# Door-opener.net
KiCad netlist of a schematic drawn in EAGLE
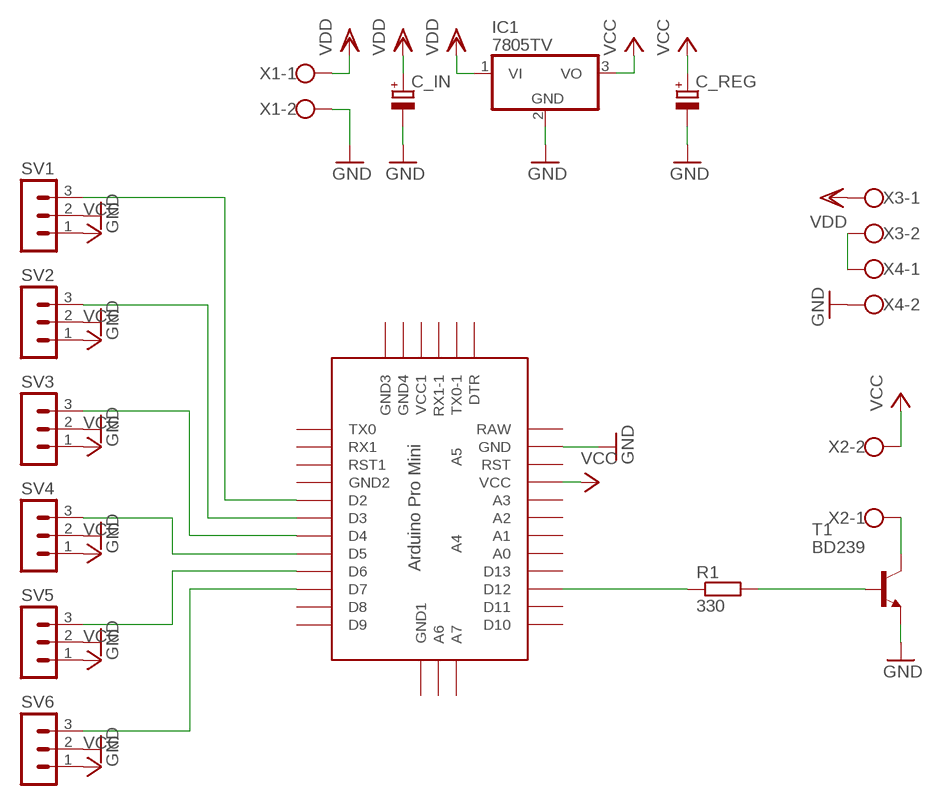
[diagram p0: schematic, sheet 1]

(export (version "E")
  (design (tool "Eeschema 10.0.6"))
  (components
    (comp (ref "C_IN")
      (value "CPOL-EUE3.5-8")
      (footprint "eagle-import:E3,5-8")
      (libsource (lib "eagle-import") (part "CPOL-EUE3.5-8"))
    )
    (comp (ref "C_REG")
      (value "CPOL-EUE3.5-8")
      (footprint "eagle-import:E3,5-8")
      (libsource (lib "eagle-import") (part "CPOL-EUE3.5-8"))
    )
    (comp (ref "IC1")
      (value "7805TV")
      (footprint "eagle-import:TO220V")
      (libsource (lib "eagle-import") (part "78TV05"))
    )
    (comp (ref "R1")
      (value "330")
      (footprint "eagle-import:0207_10")
      (libsource (lib "eagle-import") (part "R-EU_0207/10"))
    )
    (comp (ref "SV1")
      (value "MA03-1")
      (footprint "eagle-import:MA03-1")
      (libsource (lib "eagle-import") (part "MA03-1"))
    )
    (comp (ref "SV2")
      (value "MA03-1")
      (footprint "eagle-import:MA03-1")
      (libsource (lib "eagle-import") (part "MA03-1"))
    )
    (comp (ref "SV3")
      (value "MA03-1")
      (footprint "eagle-import:MA03-1")
      (libsource (lib "eagle-import") (part "MA03-1"))
    )
    (comp (ref "SV4")
      (value "MA03-1")
      (footprint "eagle-import:MA03-1")
      (libsource (lib "eagle-import") (part "MA03-1"))
    )
    (comp (ref "SV5")
      (value "MA03-1")
      (footprint "eagle-import:MA03-1")
      (libsource (lib "eagle-import") (part "MA03-1"))
    )
    (comp (ref "SV6")
      (value "MA03-1")
      (footprint "eagle-import:MA03-1")
      (libsource (lib "eagle-import") (part "MA03-1"))
    )
    (comp (ref "T1")
      (value "BD239")
      (footprint "eagle-import:TO220")
      (libsource (lib "eagle-import") (part "BD239"))
    )
    (comp (ref "U$1")
      (value "ABK-PRO-MINI")
      (footprint "eagle-import:ABK-PRO-MINI")
      (libsource (lib "eagle-import") (part "ABK-PRO-MINI"))
    )
    (comp (ref "X1")
      (value "W237-102")
      (footprint "eagle-import:W237-102")
      (fields (field (name "MPN") "237-102"))
      (libsource (lib "eagle-import") (part "W237-102"))
    )
    (comp (ref "X2")
      (value "W237-102")
      (footprint "eagle-import:W237-102")
      (fields (field (name "MPN") "237-102"))
      (libsource (lib "eagle-import") (part "W237-102"))
    )
    (comp (ref "X3")
      (value "W237-102")
      (footprint "eagle-import:W237-102")
      (fields (field (name "MPN") "237-102"))
      (libsource (lib "eagle-import") (part "W237-102"))
    )
    (comp (ref "X4")
      (value "W237-102")
      (footprint "eagle-import:W237-102")
      (fields (field (name "MPN") "237-102"))
      (libsource (lib "eagle-import") (part "W237-102"))
    )
  )
  (nets
    (net (code "1") (name "GND") (class "Default")
      (node (ref "C_IN") (pin "-") (pinfunction "-_-") (pintype "passive"))
      (node (ref "C_REG") (pin "-") (pinfunction "-_-") (pintype "passive"))
      (node (ref "IC1") (pin "2") (pinfunction "GND_2") (pintype "passive"))
      (node (ref "SV1") (pin "2") (pinfunction "2_2") (pintype "passive"))
      (node (ref "SV2") (pin "2") (pinfunction "2_2") (pintype "passive"))
      (node (ref "SV3") (pin "2") (pinfunction "2_2") (pintype "passive"))
      (node (ref "SV4") (pin "2") (pinfunction "2_2") (pintype "passive"))
      (node (ref "SV5") (pin "2") (pinfunction "2_2") (pintype "passive"))
      (node (ref "SV6") (pin "2") (pinfunction "2_2") (pintype "passive"))
      (node (ref "T1") (pin "3") (pinfunction "E_3") (pintype "passive"))
      (node (ref "U$1") (pin "GND") (pinfunction "GND_GND") (pintype "bidirectional"))
      (node (ref "X1") (pin "2") (pinfunction "KL_2") (pintype "passive"))
      (node (ref "X4") (pin "2") (pinfunction "KL_2") (pintype "passive"))
    )
    (net (code "2") (name "Net-(R1-Pad1)") (class "Default")
      (node (ref "R1") (pin "1") (pinfunction "1_1") (pintype "passive"))
      (node (ref "U$1") (pin "D12") (pinfunction "D12_D12") (pintype "bidirectional"))
    )
    (net (code "3") (name "Net-(SV1-Pad3)") (class "Default")
      (node (ref "SV1") (pin "3") (pinfunction "3_3") (pintype "passive"))
      (node (ref "U$1") (pin "D2") (pinfunction "D2_D2") (pintype "bidirectional"))
    )
    (net (code "4") (name "Net-(SV2-Pad3)") (class "Default")
      (node (ref "SV2") (pin "3") (pinfunction "3_3") (pintype "passive"))
      (node (ref "U$1") (pin "D3") (pinfunction "D3_D3") (pintype "bidirectional"))
    )
    (net (code "5") (name "Net-(SV3-Pad3)") (class "Default")
      (node (ref "SV3") (pin "3") (pinfunction "3_3") (pintype "passive"))
      (node (ref "U$1") (pin "D4") (pinfunction "D4_D4") (pintype "bidirectional"))
    )
    (net (code "6") (name "Net-(SV4-Pad3)") (class "Default")
      (node (ref "SV4") (pin "3") (pinfunction "3_3") (pintype "passive"))
      (node (ref "U$1") (pin "D5") (pinfunction "D5_D5") (pintype "bidirectional"))
    )
    (net (code "7") (name "Net-(SV5-Pad3)") (class "Default")
      (node (ref "SV5") (pin "3") (pinfunction "3_3") (pintype "passive"))
      (node (ref "U$1") (pin "D6") (pinfunction "D6_D6") (pintype "bidirectional"))
    )
    (net (code "8") (name "Net-(SV6-Pad3)") (class "Default")
      (node (ref "SV6") (pin "3") (pinfunction "3_3") (pintype "passive"))
      (node (ref "U$1") (pin "D7") (pinfunction "D7_D7") (pintype "bidirectional"))
    )
    (net (code "9") (name "Net-(T1-B)") (class "Default")
      (node (ref "R1") (pin "2") (pinfunction "2_2") (pintype "passive"))
      (node (ref "T1") (pin "1") (pinfunction "B_1") (pintype "passive"))
    )
    (net (code "10") (name "Net-(T1-C)") (class "Default")
      (node (ref "T1") (pin "2") (pinfunction "C_2") (pintype "passive"))
      (node (ref "X2") (pin "1") (pinfunction "KL_1") (pintype "passive"))
    )
    (net (code "11") (name "Net-(X3B-KL)") (class "Default")
      (node (ref "X3") (pin "2") (pinfunction "KL_2") (pintype "passive"))
      (node (ref "X4") (pin "1") (pinfunction "KL_1") (pintype "passive"))
    )
    (net (code "12") (name "VCC") (class "Default")
      (node (ref "C_REG") (pin "+") (pinfunction "+_+") (pintype "passive"))
      (node (ref "IC1") (pin "3") (pinfunction "VO_3") (pintype "passive"))
      (node (ref "SV1") (pin "1") (pinfunction "1_1") (pintype "passive"))
      (node (ref "SV2") (pin "1") (pinfunction "1_1") (pintype "passive"))
      (node (ref "SV3") (pin "1") (pinfunction "1_1") (pintype "passive"))
      (node (ref "SV4") (pin "1") (pinfunction "1_1") (pintype "passive"))
      (node (ref "SV5") (pin "1") (pinfunction "1_1") (pintype "passive"))
      (node (ref "SV6") (pin "1") (pinfunction "1_1") (pintype "passive"))
      (node (ref "U$1") (pin "VCC") (pinfunction "VCC_VCC") (pintype "bidirectional"))
      (node (ref "X2") (pin "2") (pinfunction "KL_2") (pintype "passive"))
    )
    (net (code "13") (name "VDD") (class "Default")
      (node (ref "C_IN") (pin "+") (pinfunction "+_+") (pintype "passive"))
      (node (ref "IC1") (pin "1") (pinfunction "VI_1") (pintype "input"))
      (node (ref "X1") (pin "1") (pinfunction "KL_1") (pintype "passive"))
      (node (ref "X3") (pin "1") (pinfunction "KL_1") (pintype "passive"))
    )
    (net (code "14") (name "unconnected-(U$1-GND1-PadGND4)") (class "Default")
      (node (ref "U$1") (pin "GND4") (pinfunction "GND1_GND4") (pintype "bidirectional"))
    )
    (net (code "15") (name "unconnected-(U$1-GND2-PadGND1)") (class "Default")
      (node (ref "U$1") (pin "GND1") (pinfunction "GND2_GND1") (pintype "bidirectional"))
    )
    (net (code "16") (name "unconnected-(U$1-GND3-PadGND2)") (class "Default")
      (node (ref "U$1") (pin "GND2") (pinfunction "GND3_GND2") (pintype "bidirectional"))
    )
    (net (code "17") (name "unconnected-(U$1-GND4-PadGND3)") (class "Default")
      (node (ref "U$1") (pin "GND3") (pinfunction "GND4_GND3") (pintype "bidirectional"))
    )
    (net (code "18") (name "unconnected-(U$1-PadA0)") (class "Default")
      (node (ref "U$1") (pin "A0") (pinfunction "A0_A0") (pintype "bidirectional"))
    )
    (net (code "19") (name "unconnected-(U$1-PadA1)") (class "Default")
      (node (ref "U$1") (pin "A1") (pinfunction "A1_A1") (pintype "bidirectional"))
    )
    (net (code "20") (name "unconnected-(U$1-PadA2)") (class "Default")
      (node (ref "U$1") (pin "A2") (pinfunction "A2_A2") (pintype "bidirectional"))
    )
    (net (code "21") (name "unconnected-(U$1-PadA3)") (class "Default")
      (node (ref "U$1") (pin "A3") (pinfunction "A3_A3") (pintype "bidirectional"))
    )
    (net (code "22") (name "unconnected-(U$1-PadA4)") (class "Default")
      (node (ref "U$1") (pin "A4") (pinfunction "A4_A4") (pintype "bidirectional"))
    )
    (net (code "23") (name "unconnected-(U$1-PadA5)") (class "Default")
      (node (ref "U$1") (pin "A5") (pinfunction "A5_A5") (pintype "bidirectional"))
    )
    (net (code "24") (name "unconnected-(U$1-PadA6)") (class "Default")
      (node (ref "U$1") (pin "A6") (pinfunction "A6_A6") (pintype "bidirectional"))
    )
    (net (code "25") (name "unconnected-(U$1-PadA7)") (class "Default")
      (node (ref "U$1") (pin "A7") (pinfunction "A7_A7") (pintype "bidirectional"))
    )
    (net (code "26") (name "unconnected-(U$1-PadD8)") (class "Default")
      (node (ref "U$1") (pin "D8") (pinfunction "D8_D8") (pintype "bidirectional"))
    )
    (net (code "27") (name "unconnected-(U$1-PadD9)") (class "Default")
      (node (ref "U$1") (pin "D9") (pinfunction "D9_D9") (pintype "bidirectional"))
    )
    (net (code "28") (name "unconnected-(U$1-PadD10)") (class "Default")
      (node (ref "U$1") (pin "D10") (pinfunction "D10_D10") (pintype "bidirectional"))
    )
    (net (code "29") (name "unconnected-(U$1-PadD11)") (class "Default")
      (node (ref "U$1") (pin "D11") (pinfunction "D11_D11") (pintype "bidirectional"))
    )
    (net (code "30") (name "unconnected-(U$1-PadD13)") (class "Default")
      (node (ref "U$1") (pin "D13") (pinfunction "D13_D13") (pintype "bidirectional"))
    )
    (net (code "31") (name "unconnected-(U$1-PadDTR)") (class "Default")
      (node (ref "U$1") (pin "DTR") (pinfunction "DTR_DTR") (pintype "bidirectional"))
    )
    (net (code "32") (name "unconnected-(U$1-PadRAW)") (class "Default")
      (node (ref "U$1") (pin "RAW") (pinfunction "RAW_RAW") (pintype "bidirectional"))
    )
    (net (code "33") (name "unconnected-(U$1-PadRST)") (class "Default")
      (node (ref "U$1") (pin "RST") (pinfunction "RST_RST") (pintype "bidirectional"))
    )
    (net (code "34") (name "unconnected-(U$1-PadRST1)") (class "Default")
      (node (ref "U$1") (pin "RST1") (pinfunction "RST1_RST1") (pintype "bidirectional"))
    )
    (net (code "35") (name "unconnected-(U$1-PadRX1)") (class "Default")
      (node (ref "U$1") (pin "RX1") (pinfunction "RX1_RX1") (pintype "bidirectional"))
    )
    (net (code "36") (name "unconnected-(U$1-PadRX1-1)") (class "Default")
      (node (ref "U$1") (pin "RX1-1") (pinfunction "RX1-1_RX1-1") (pintype "bidirectional"))
    )
    (net (code "37") (name "unconnected-(U$1-PadTX0)") (class "Default")
      (node (ref "U$1") (pin "TX0") (pinfunction "TX0_TX0") (pintype "bidirectional"))
    )
    (net (code "38") (name "unconnected-(U$1-PadTX0-1)") (class "Default")
      (node (ref "U$1") (pin "TX0-1") (pinfunction "TX0-1_TX0-1") (pintype "bidirectional"))
    )
    (net (code "39") (name "unconnected-(U$1-PadVCC1)") (class "Default")
      (node (ref "U$1") (pin "VCC1") (pinfunction "VCC1_VCC1") (pintype "bidirectional"))
    )
  )
)
